# INT_REG.net
KiCad netlist of a schematic drawn in Altium Designer
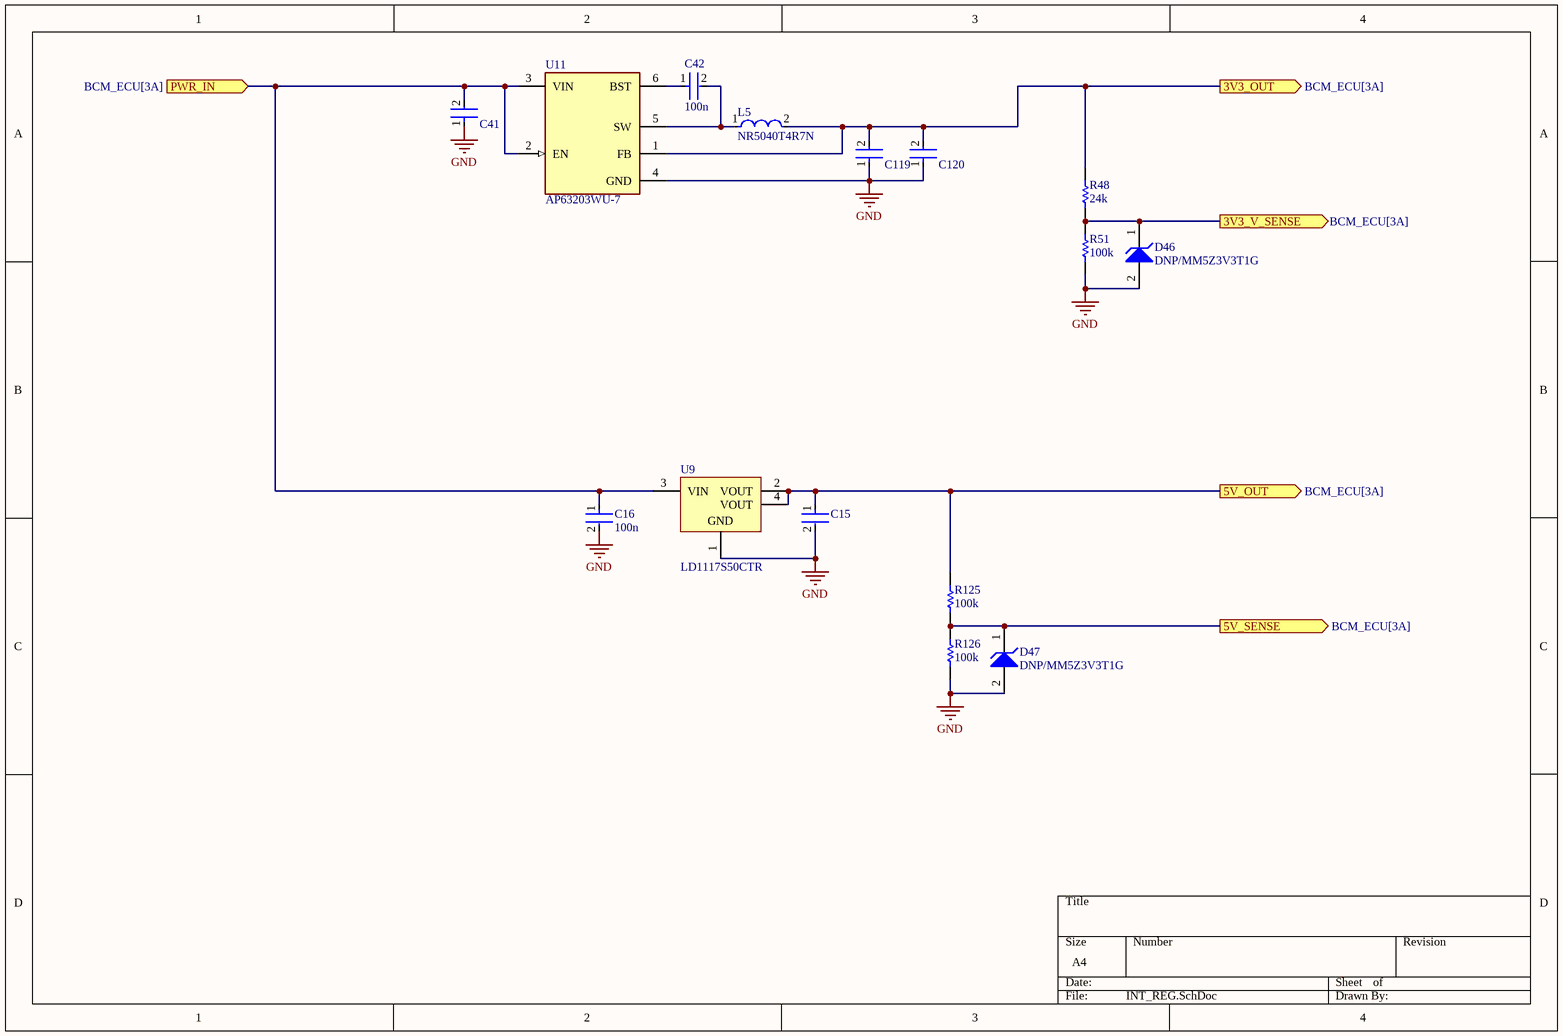
[diagram p0: INT_REG.SchDoc]

(export (version "E")
  (design (tool "Eeschema 10.0.6"))
  (components
    (comp (ref "C15")
      (value "GRM188R60J106ME47D")
      (footprint "FP-GRM188-0_1-e0_2_0_55-IPC_A")
      (description "Chip Multilayer Ceramic Capacitors for General Purpose, 0603, 10uF, X5R, 15%, 20%, 6.3V")
      (fields (field (name "VOLTAGE") "6.3V") (field (name "TOLERANCE") "20%"))
      (libsource (lib "Altium Content Vault") (part "02cd4be3c70576c341d710602a673aa"))
    )
    (comp (ref "C16")
      (value "100n")
      (footprint "FP-0402-L_1_0_0_05-W_0_5-IPC_A")
      (description "LARGE PADS, 0402 CAP, CHANGE COMMENT TO MATCH REAL P/N")
      (libsource (lib "Space Concordia") (part "b4654b650e69147ec39a6b967a45e02"))
    )
    (comp (ref "C41")
      (value "GRM21BR61E226ME44L")
      (footprint "FP-GRM21B-0_2-e0_2_0_7-IPC_B")
      (description "Chip Multilayer Ceramic Capacitors for General Purpose, 0805, 22uF, X5R, 15%, 20%, 25V")
      (fields (field (name "TOLERANCE") "20%") (field (name "VOLTAGE") "25V"))
      (libsource (lib "Altium Content Vault") (part "b4654b650e69147ec39a6b967a45e02"))
    )
    (comp (ref "C42")
      (value "100n")
      (footprint "FP-0402-L_1_0_0_05-W_0_5-IPC_A")
      (description "LARGE PADS, 0402 CAP, CHANGE COMMENT TO MATCH REAL P/N")
      (libsource (lib "Space Concordia") (part "b4654b650e69147ec39a6b967a45e02"))
    )
    (comp (ref "C119")
      (value "GRM21BR61E226ME44L")
      (footprint "FP-GRM21B-0_2-e0_2_0_7-IPC_B")
      (description "Chip Multilayer Ceramic Capacitors for General Purpose, 0805, 22uF, X5R, 15%, 20%, 25V")
      (fields (field (name "TOLERANCE") "20%") (field (name "VOLTAGE") "25V"))
      (libsource (lib "Altium Content Vault") (part "b4654b650e69147ec39a6b967a45e02"))
    )
    (comp (ref "C120")
      (value "GRM21BR61E226ME44L")
      (footprint "FP-GRM21B-0_2-e0_2_0_7-IPC_B")
      (description "Chip Multilayer Ceramic Capacitors for General Purpose, 0805, 22uF, X5R, 15%, 20%, 25V")
      (fields (field (name "TOLERANCE") "20%") (field (name "VOLTAGE") "25V"))
      (libsource (lib "Altium Content Vault") (part "b4654b650e69147ec39a6b967a45e02"))
    )
    (comp (ref "D46")
      (value "DNP/MM5Z3V3T1G")
      (footprint "ONSC-SOD-523-2-502-01_V")
      (description "Zener Voltage Regulator, 500 mW, 2-Pin SOD-523, Pb-Free, Tape and Reel")
      (fields (field (name "MANUFACTURER") "On Semiconductor") (field (name "PARTNUMBER") "MM5Z3V3T1G"))
      (libsource (lib "Altium Content Vault") (part "ONSC-K1A2-2"))
    )
    (comp (ref "D47")
      (value "DNP/MM5Z3V3T1G")
      (footprint "ONSC-SOD-523-2-502-01_V")
      (description "Zener Voltage Regulator, 500 mW, 2-Pin SOD-523, Pb-Free, Tape and Reel")
      (fields (field (name "MANUFACTURER") "On Semiconductor") (field (name "PARTNUMBER") "MM5Z3V3T1G"))
      (libsource (lib "Altium Content Vault") (part "ONSC-K1A2-2"))
    )
    (comp (ref "L5")
      (value "NR5040T4R7N")
      (footprint "FP-NR5040-H_4_1-MFG")
      (description "SMD Power Inductors 4.7uH ±30% 3.1A 37.7mΩ")
      (fields (field (name "TOLERANCE") "30%"))
      (libsource (lib "Altium Content Vault") (part "725321dda6339637d4d059423bc1c3c"))
    )
    (comp (ref "R48")
      (value "24k")
      (footprint "R0603B")
      (description "Resistor")
      (libsource (lib "Space Concordia") (part "Resistor"))
    )
    (comp (ref "R51")
      (value "100k")
      (footprint "R0603B")
      (description "Resistor")
      (libsource (lib "Space Concordia") (part "Resistor"))
    )
    (comp (ref "R125")
      (value "100k")
      (footprint "R0603B")
      (description "Resistor")
      (libsource (lib "Space Concordia") (part "Resistor"))
    )
    (comp (ref "R126")
      (value "100k")
      (footprint "R0603B")
      (description "Resistor")
      (libsource (lib "Space Concordia") (part "Resistor"))
    )
    (comp (ref "U9")
      (value "LD1117S50CTR")
      (footprint "SOT-223_N")
      (description "Fixed Low Drop Positive Voltage Regulator, 5V, 4-Pin SOT-223, Tape and Reel")
      (libsource (lib "Altium Content Vault") (part "PM-REG-LD1117-SOT4"))
    )
    (comp (ref "U11")
      (value "AP63203WU-7")
      (footprint "FP-TSOT26-MFG")
      (description "IC REG BUCK 3.3V 2A TSOT26")
      (fields
        (field (name "MANUFACTURER") "Diodes Inc.")
        (field (name "OCTOPART") "https://octopart.com/ap63203wu-7-diodes+inc.-98099550")
      )
      (libsource (lib "Altium Content Vault") (part "0e61c2974d7114b43f01ef96ae2e524"))
    )
  )
  (nets
    (net (code "1") (name "/3V3_OUT") (class "Default")
      (node (ref "C119") (pin "2") (pinfunction "2_2") (pintype "passive"))
      (node (ref "C120") (pin "2") (pinfunction "2_2") (pintype "passive"))
      (node (ref "L5") (pin "2") (pinfunction "2_2") (pintype "passive"))
      (node (ref "R48") (pin "1") (pinfunction "1_1") (pintype "passive"))
      (node (ref "U11") (pin "1") (pinfunction "FB_1") (pintype "passive"))
    )
    (net (code "2") (name "/3V3_V_SENSE") (class "Default")
      (node (ref "D46") (pin "1") (pinfunction "K_1") (pintype "passive"))
      (node (ref "R48") (pin "2") (pinfunction "2_2") (pintype "passive"))
      (node (ref "R51") (pin "1") (pinfunction "1_1") (pintype "passive"))
    )
    (net (code "3") (name "/5V_OUT") (class "Default")
      (node (ref "C15") (pin "1") (pinfunction "1_1") (pintype "passive"))
      (node (ref "R125") (pin "1") (pinfunction "1_1") (pintype "passive"))
      (node (ref "U9") (pin "2") (pinfunction "VOUT_2") (pintype "power_in"))
      (node (ref "U9") (pin "4") (pinfunction "VOUT_4") (pintype "power_in"))
    )
    (net (code "4") (name "/5V_SENSE") (class "Default")
      (node (ref "D47") (pin "1") (pinfunction "K_1") (pintype "passive"))
      (node (ref "R125") (pin "2") (pinfunction "2_2") (pintype "passive"))
      (node (ref "R126") (pin "1") (pinfunction "1_1") (pintype "passive"))
    )
    (net (code "5") (name "/PWR_IN") (class "Default")
      (node (ref "C16") (pin "1") (pinfunction "1_1") (pintype "passive"))
      (node (ref "C41") (pin "2") (pinfunction "2_2") (pintype "passive"))
      (node (ref "U11") (pin "2") (pinfunction "EN_2") (pintype "input"))
      (node (ref "U11") (pin "3") (pinfunction "VIN_3") (pintype "power_in"))
      (node (ref "U9") (pin "3") (pinfunction "VIN_3") (pintype "power_in"))
    )
    (net (code "6") (name "GND") (class "Default")
      (node (ref "C119") (pin "1") (pinfunction "1_1") (pintype "passive"))
      (node (ref "C120") (pin "1") (pinfunction "1_1") (pintype "passive"))
      (node (ref "C15") (pin "2") (pinfunction "2_2") (pintype "passive"))
      (node (ref "C16") (pin "2") (pinfunction "2_2") (pintype "passive"))
      (node (ref "C41") (pin "1") (pinfunction "1_1") (pintype "passive"))
      (node (ref "D46") (pin "2") (pinfunction "A_2") (pintype "passive"))
      (node (ref "D47") (pin "2") (pinfunction "A_2") (pintype "passive"))
      (node (ref "R126") (pin "2") (pinfunction "2_2") (pintype "passive"))
      (node (ref "R51") (pin "2") (pinfunction "2_2") (pintype "passive"))
      (node (ref "U11") (pin "4") (pinfunction "GND_4") (pintype "power_in"))
      (node (ref "U9") (pin "1") (pinfunction "GND_1") (pintype "power_in"))
    )
    (net (code "7") (name "Net-(U11-BST)") (class "Default")
      (node (ref "C42") (pin "1") (pinfunction "1_1") (pintype "passive"))
      (node (ref "U11") (pin "6") (pinfunction "BST_6") (pintype "passive"))
    )
    (net (code "8") (name "Net-(U11-SW)") (class "Default")
      (node (ref "C42") (pin "2") (pinfunction "2_2") (pintype "passive"))
      (node (ref "L5") (pin "1") (pinfunction "1_1") (pintype "passive"))
      (node (ref "U11") (pin "5") (pinfunction "SW_5") (pintype "passive"))
    )
  )
)
